# DebugInterface.net
KiCad netlist of a schematic drawn in Altium Designer
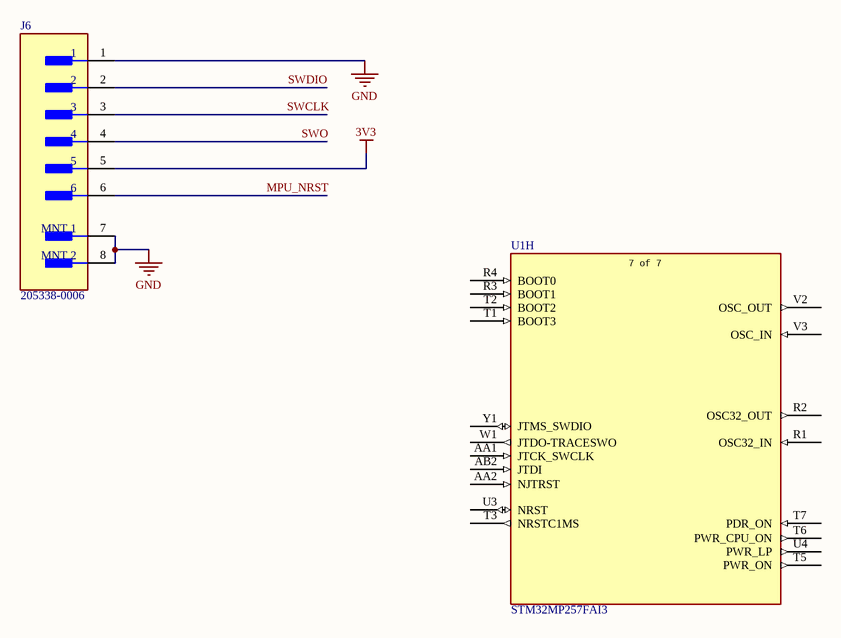
[diagram p0: DebugInterface.SchDoc]

(export (version "E")
  (design (tool "Eeschema 10.0.6"))
  (components
    (comp (ref "J6")
      (value "205338-0006")
      (footprint "FP-2053380006-MFG")
      (libsource (lib "Altium Content Vault") (part "ed24c53d9ba001d1a2a686240a95171"))
    )
    (comp (ref "U1")
      (value "STM32MP257FAI3")
      (footprint "TFBGA436_STM")
      (fields (field (name "COPYRIGHT") "Copyright (C) 2025 Ultra Librarian. All rights reserved."))
      (libsource (lib "STeRG-ICs-Standard") (part "STM32MP257FAI3"))
    )
  )
  (nets
    (net (code "1") (name "/MPU_NRST") (class "Default")
      (node (ref "J6") (pin "6") (pinfunction "6_6") (pintype "passive"))
    )
    (net (code "2") (name "/SWCLK") (class "Default")
      (node (ref "J6") (pin "3") (pinfunction "3_3") (pintype "passive"))
    )
    (net (code "3") (name "/SWDIO") (class "Default")
      (node (ref "J6") (pin "2") (pinfunction "2_2") (pintype "passive"))
    )
    (net (code "4") (name "/SWO") (class "Default")
      (node (ref "J6") (pin "4") (pinfunction "4_4") (pintype "passive"))
    )
    (net (code "5") (name "3V3") (class "Default")
      (node (ref "J6") (pin "5") (pinfunction "5_5") (pintype "passive"))
    )
    (net (code "6") (name "GND") (class "Default")
      (node (ref "J6") (pin "1") (pinfunction "1_1") (pintype "passive"))
      (node (ref "J6") (pin "7") (pinfunction "MNT_1_7") (pintype "passive"))
      (node (ref "J6") (pin "8") (pinfunction "MNT_2_8") (pintype "passive"))
    )
    (net (code "7") (name "unconnected-(U1H-BOOT0-PadR4)") (class "Default")
      (node (ref "U1") (pin "R4") (pinfunction "BOOT0_R4") (pintype "input"))
    )
    (net (code "8") (name "unconnected-(U1H-BOOT1-PadR3)") (class "Default")
      (node (ref "U1") (pin "R3") (pinfunction "BOOT1_R3") (pintype "input"))
    )
    (net (code "9") (name "unconnected-(U1H-BOOT2-PadT2)") (class "Default")
      (node (ref "U1") (pin "T2") (pinfunction "BOOT2_T2") (pintype "input"))
    )
    (net (code "10") (name "unconnected-(U1H-BOOT3-PadT1)") (class "Default")
      (node (ref "U1") (pin "T1") (pinfunction "BOOT3_T1") (pintype "input"))
    )
    (net (code "11") (name "unconnected-(U1H-JTCK_SWCLK-PadAA1)") (class "Default")
      (node (ref "U1") (pin "AA1") (pinfunction "JTCK_SWCLK_AA1") (pintype "input"))
    )
    (net (code "12") (name "unconnected-(U1H-JTDI-PadAB2)") (class "Default")
      (node (ref "U1") (pin "AB2") (pinfunction "JTDI_AB2") (pintype "input"))
    )
    (net (code "13") (name "unconnected-(U1H-JTDO-TRACESWO-PadW1)") (class "Default")
      (node (ref "U1") (pin "W1") (pinfunction "JTDO-TRACESWO_W1") (pintype "output"))
    )
    (net (code "14") (name "unconnected-(U1H-JTMS_SWDIO-PadY1)") (class "Default")
      (node (ref "U1") (pin "Y1") (pinfunction "JTMS_SWDIO_Y1") (pintype "bidirectional"))
    )
    (net (code "15") (name "unconnected-(U1H-NJTRST-PadAA2)") (class "Default")
      (node (ref "U1") (pin "AA2") (pinfunction "NJTRST_AA2") (pintype "input"))
    )
    (net (code "16") (name "unconnected-(U1H-NRST-PadU3)") (class "Default")
      (node (ref "U1") (pin "U3") (pinfunction "NRST_U3") (pintype "bidirectional"))
    )
    (net (code "17") (name "unconnected-(U1H-NRSTC1MS-PadT3)") (class "Default")
      (node (ref "U1") (pin "T3") (pinfunction "NRSTC1MS_T3") (pintype "output"))
    )
    (net (code "18") (name "unconnected-(U1H-OSC32_IN-PadR1)") (class "Default")
      (node (ref "U1") (pin "R1") (pinfunction "OSC32_IN_R1") (pintype "input"))
    )
    (net (code "19") (name "unconnected-(U1H-OSC32_OUT-PadR2)") (class "Default")
      (node (ref "U1") (pin "R2") (pinfunction "OSC32_OUT_R2") (pintype "output"))
    )
    (net (code "20") (name "unconnected-(U1H-OSC_IN-PadV3)") (class "Default")
      (node (ref "U1") (pin "V3") (pinfunction "OSC_IN_V3") (pintype "input"))
    )
    (net (code "21") (name "unconnected-(U1H-OSC_OUT-PadV2)") (class "Default")
      (node (ref "U1") (pin "V2") (pinfunction "OSC_OUT_V2") (pintype "output"))
    )
    (net (code "22") (name "unconnected-(U1H-PDR_ON-PadT7)") (class "Default")
      (node (ref "U1") (pin "T7") (pinfunction "PDR_ON_T7") (pintype "input"))
    )
    (net (code "23") (name "unconnected-(U1H-PWR_CPU_ON-PadT6)") (class "Default")
      (node (ref "U1") (pin "T6") (pinfunction "PWR_CPU_ON_T6") (pintype "output"))
    )
    (net (code "24") (name "unconnected-(U1H-PWR_LP-PadU4)") (class "Default")
      (node (ref "U1") (pin "U4") (pinfunction "PWR_LP_U4") (pintype "output"))
    )
    (net (code "25") (name "unconnected-(U1H-PWR_ON-PadT5)") (class "Default")
      (node (ref "U1") (pin "T5") (pinfunction "PWR_ON_T5") (pintype "output"))
    )
  )
)
